# durtest-ripup.net
KiCad netlist of a schematic drawn in EAGLE
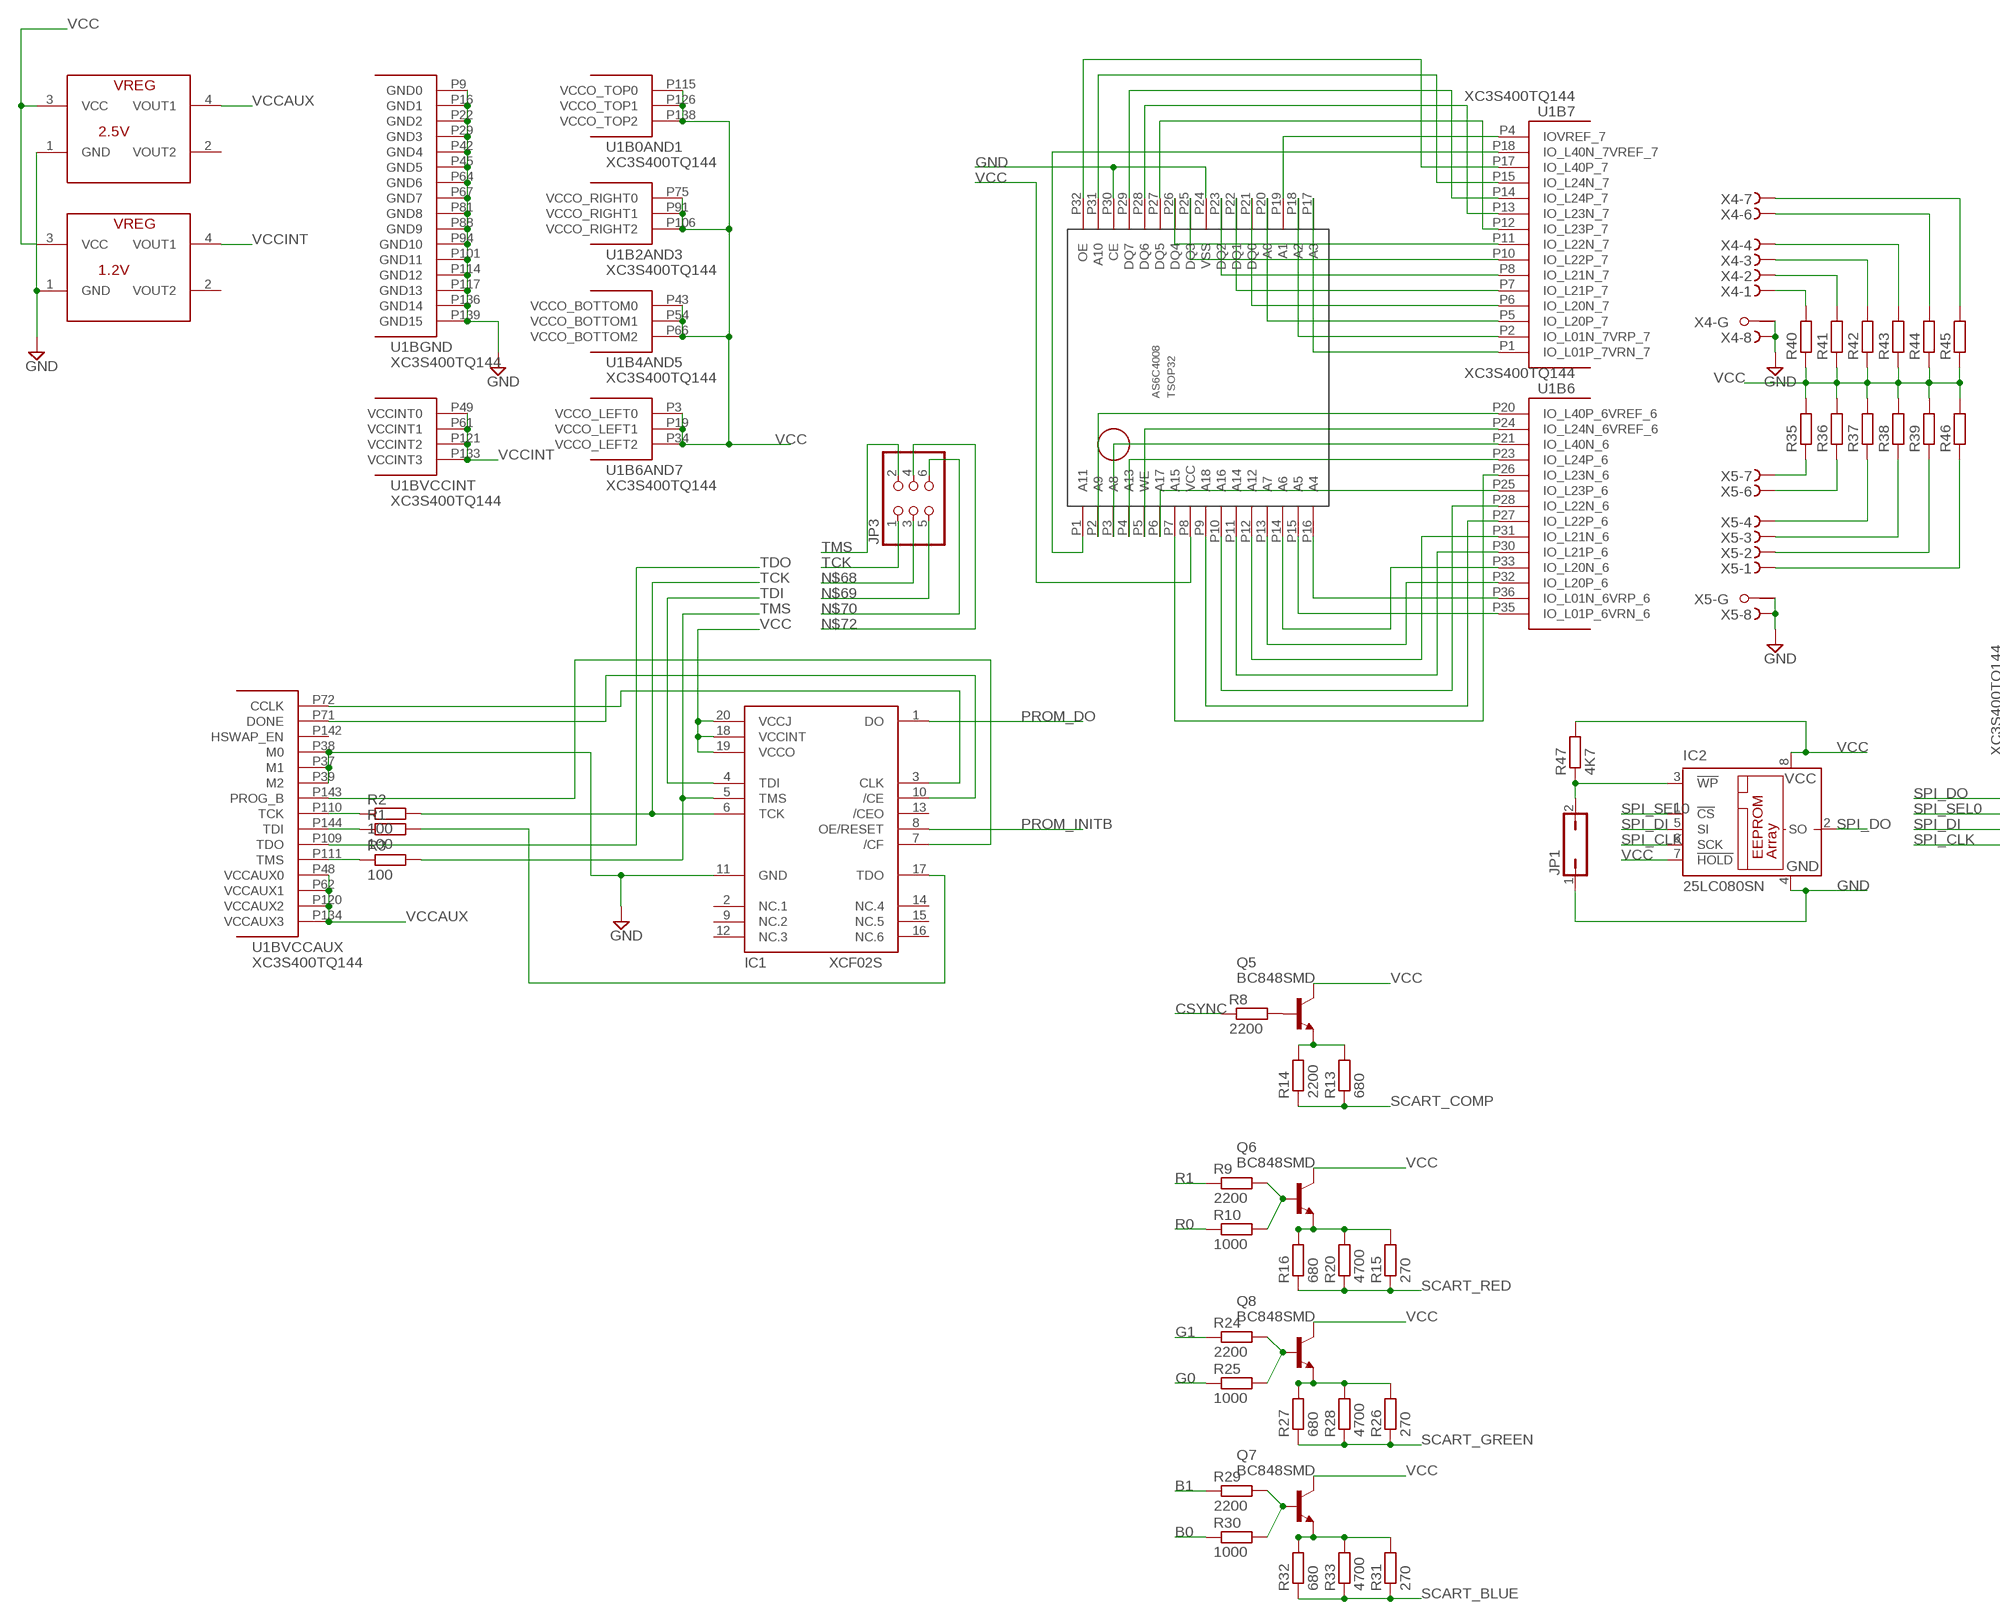
[diagram p0: schematic, sheet 1, part 1 of 2]
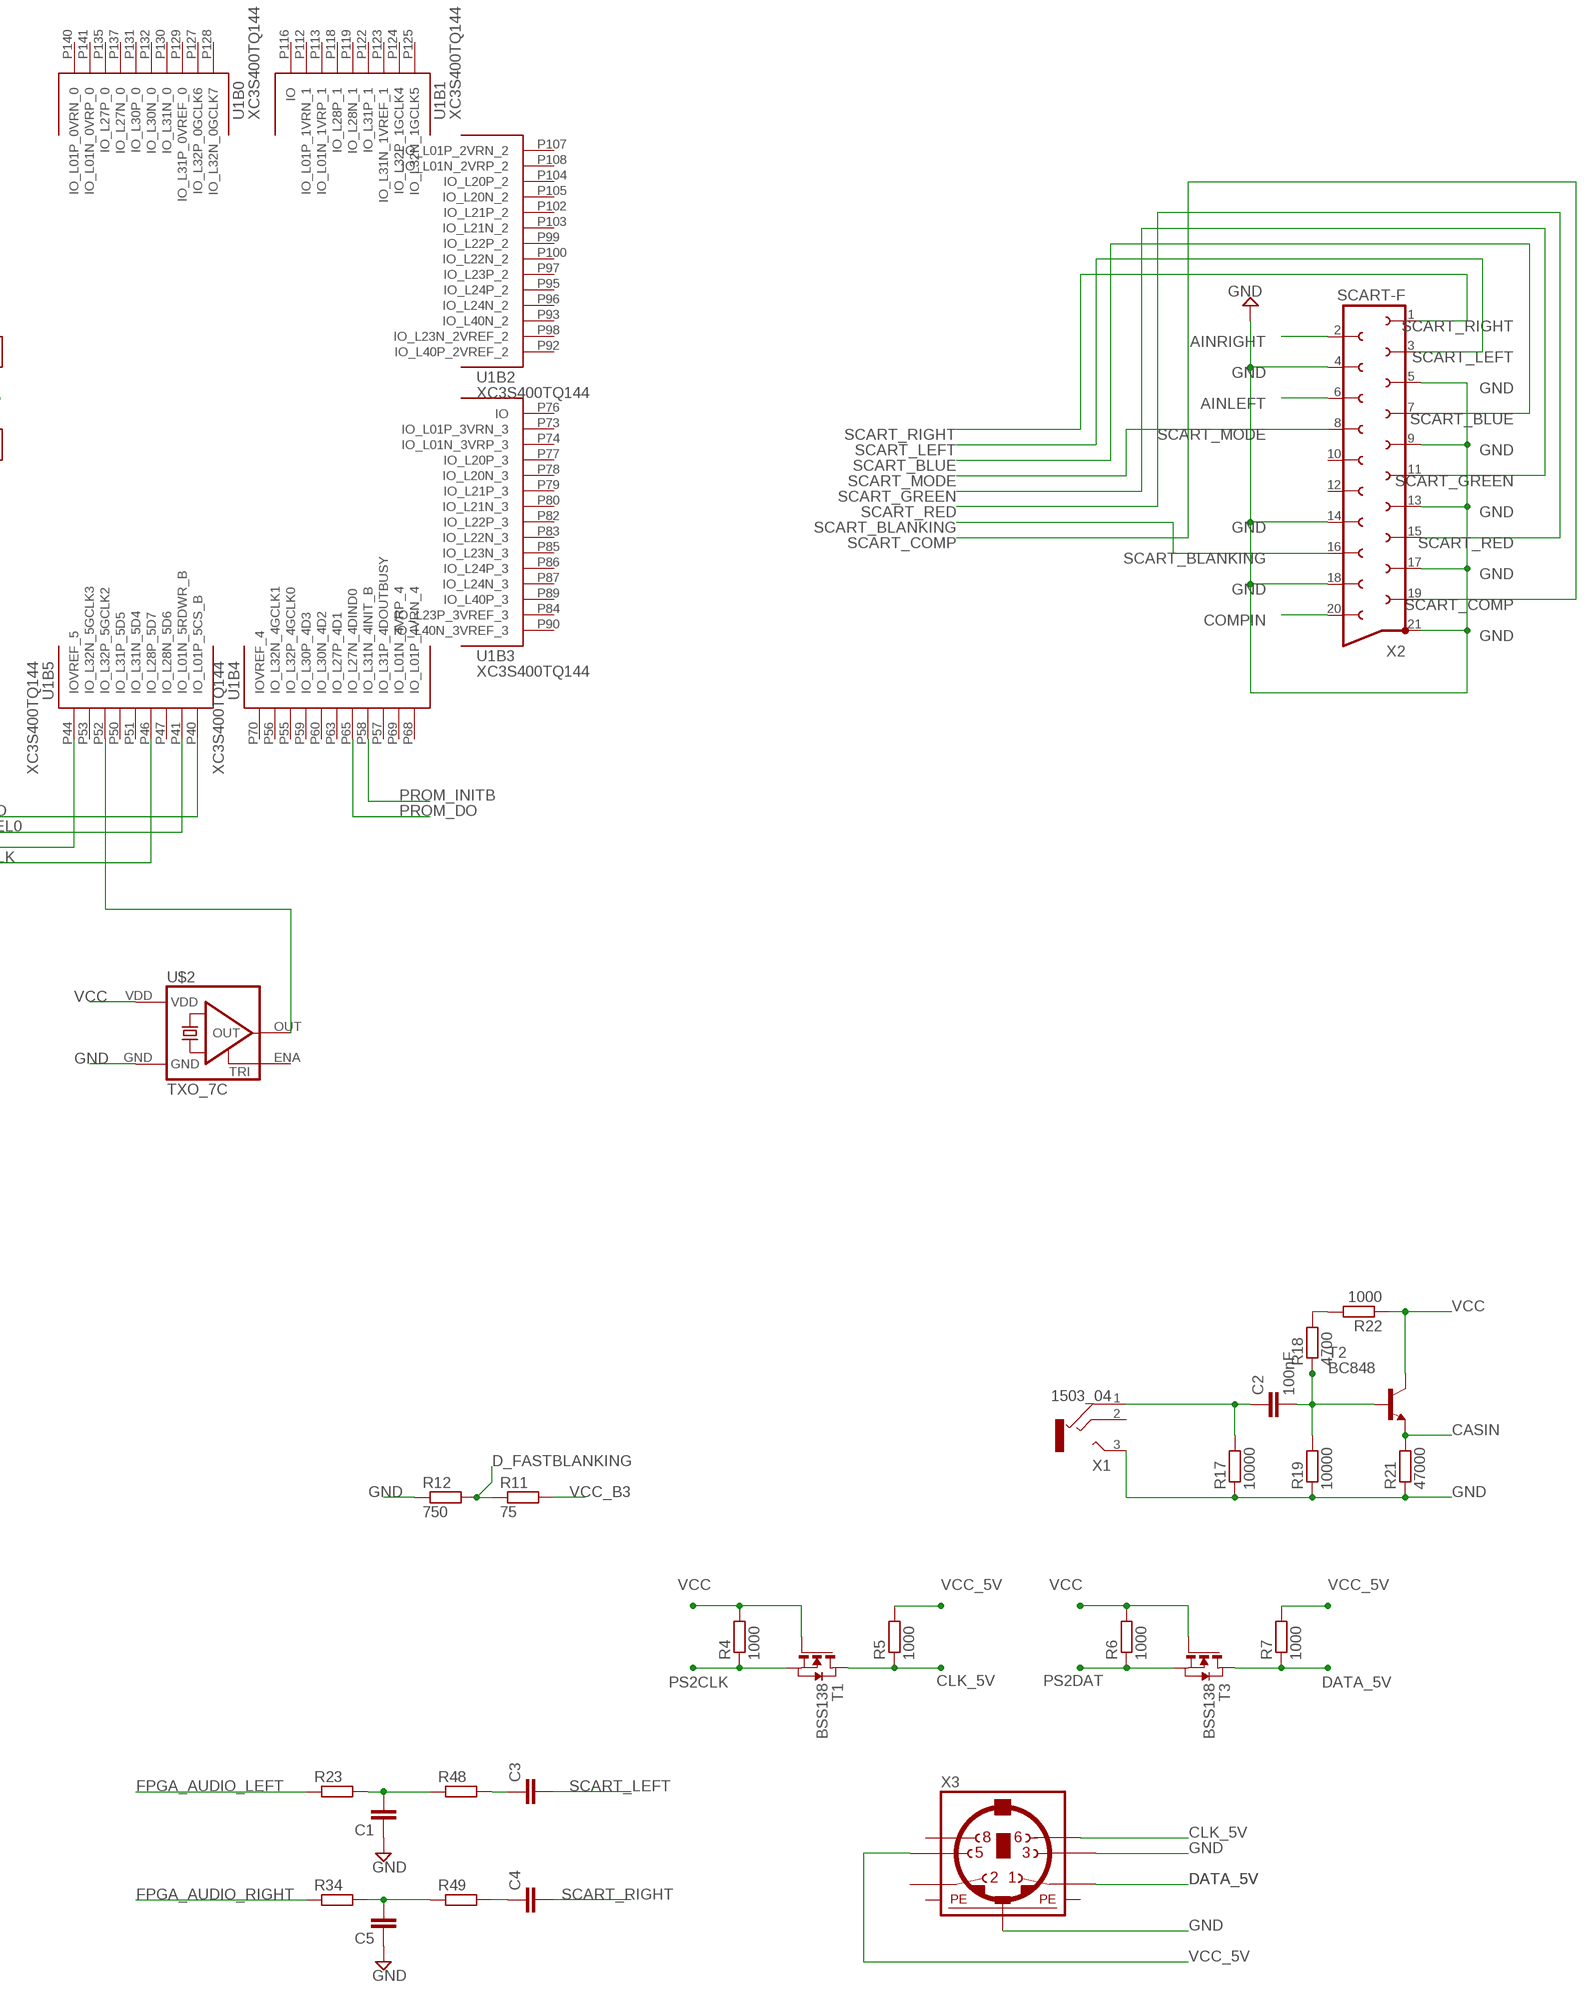
[diagram p1: schematic, sheet 1, part 2 of 2]

(export (version "E")
  (design (tool "Eeschema 10.0.6"))
  (components
    (comp (ref "C1")
      (value "C-EUC0603")
      (footprint "eagle-import:C0603")
      (libsource (lib "eagle-import") (part "C-EUC0603"))
    )
    (comp (ref "C2")
      (value "100nF")
      (footprint "eagle-import:C0603")
      (libsource (lib "eagle-import") (part "C-EUC0603"))
    )
    (comp (ref "C3")
      (value "C-EUC0603")
      (footprint "eagle-import:C0603")
      (libsource (lib "eagle-import") (part "C-EUC0603"))
    )
    (comp (ref "C4")
      (value "C-EUC0603")
      (footprint "eagle-import:C0603")
      (libsource (lib "eagle-import") (part "C-EUC0603"))
    )
    (comp (ref "C5")
      (value "C-EUC0603")
      (footprint "eagle-import:C0603")
      (libsource (lib "eagle-import") (part "C-EUC0603"))
    )
    (comp (ref "IC1")
      (value "XCF02S")
      (footprint "eagle-import:VO20")
      (libsource (lib "eagle-import") (part "XCF02S"))
    )
    (comp (ref "IC2")
      (value "25LC080SN")
      (footprint "eagle-import:SO-08")
      (fields (field (name "MF") "MICROCHIP") (field (name "MPN") "25LC080/SN"))
      (libsource (lib "eagle-import") (part "25SNLC080"))
    )
    (comp (ref "JP1")
      (value "JP1Q")
      (footprint "eagle-import:JP1")
      (libsource (lib "eagle-import") (part "JP1Q"))
    )
    (comp (ref "JP3")
      (value "PINHD-2X3")
      (footprint "eagle-import:2X03")
      (libsource (lib "eagle-import") (part "PINHD-2X3"))
    )
    (comp (ref "Q5")
      (value "BC848SMD")
      (footprint "eagle-import:SOT23")
      (libsource (lib "eagle-import") (part "BC848SMD"))
    )
    (comp (ref "Q6")
      (value "BC848SMD")
      (footprint "eagle-import:SOT23")
      (libsource (lib "eagle-import") (part "BC848SMD"))
    )
    (comp (ref "Q7")
      (value "BC848SMD")
      (footprint "eagle-import:SOT23")
      (libsource (lib "eagle-import") (part "BC848SMD"))
    )
    (comp (ref "Q8")
      (value "BC848SMD")
      (footprint "eagle-import:SOT23")
      (libsource (lib "eagle-import") (part "BC848SMD"))
    )
    (comp (ref "R1")
      (value "100")
      (footprint "eagle-import:R0805")
      (libsource (lib "eagle-import") (part "R-EU_R0805"))
    )
    (comp (ref "R2")
      (value "100")
      (footprint "eagle-import:R0805")
      (libsource (lib "eagle-import") (part "R-EU_R0805"))
    )
    (comp (ref "R3")
      (value "100")
      (footprint "eagle-import:R0805")
      (libsource (lib "eagle-import") (part "R-EU_R0805"))
    )
    (comp (ref "R4")
      (value "1000")
      (footprint "eagle-import:R0805")
      (libsource (lib "eagle-import") (part "R-EU_R0805"))
    )
    (comp (ref "R5")
      (value "1000")
      (footprint "eagle-import:R0805")
      (libsource (lib "eagle-import") (part "R-EU_R0805"))
    )
    (comp (ref "R6")
      (value "1000")
      (footprint "eagle-import:R0805")
      (libsource (lib "eagle-import") (part "R-EU_R0805"))
    )
    (comp (ref "R7")
      (value "1000")
      (footprint "eagle-import:R0805")
      (libsource (lib "eagle-import") (part "R-EU_R0805"))
    )
    (comp (ref "R8")
      (value "2200")
      (footprint "eagle-import:R0805")
      (libsource (lib "eagle-import") (part "R-EU_R0805"))
    )
    (comp (ref "R9")
      (value "2200")
      (footprint "eagle-import:R0805")
      (libsource (lib "eagle-import") (part "R-EU_R0805"))
    )
    (comp (ref "R10")
      (value "1000")
      (footprint "eagle-import:R0805")
      (libsource (lib "eagle-import") (part "R-EU_R0805"))
    )
    (comp (ref "R11")
      (value "75")
      (footprint "eagle-import:R0805")
      (libsource (lib "eagle-import") (part "R-EU_R0805"))
    )
    (comp (ref "R12")
      (value "750")
      (footprint "eagle-import:R0805")
      (libsource (lib "eagle-import") (part "R-EU_R0805"))
    )
    (comp (ref "R13")
      (value "680")
      (footprint "eagle-import:R0805")
      (libsource (lib "eagle-import") (part "R-EU_R0805"))
    )
    (comp (ref "R14")
      (value "2200")
      (footprint "eagle-import:R0805")
      (libsource (lib "eagle-import") (part "R-EU_R0805"))
    )
    (comp (ref "R15")
      (value "270")
      (footprint "eagle-import:R0805")
      (libsource (lib "eagle-import") (part "R-EU_R0805"))
    )
    (comp (ref "R16")
      (value "680")
      (footprint "eagle-import:R0805")
      (libsource (lib "eagle-import") (part "R-EU_R0805"))
    )
    (comp (ref "R17")
      (value "10000")
      (footprint "eagle-import:R0805")
      (libsource (lib "eagle-import") (part "R-EU_R0805"))
    )
    (comp (ref "R18")
      (value "4700")
      (footprint "eagle-import:R0805")
      (libsource (lib "eagle-import") (part "R-EU_R0805"))
    )
    (comp (ref "R19")
      (value "10000")
      (footprint "eagle-import:R0805")
      (libsource (lib "eagle-import") (part "R-EU_R0805"))
    )
    (comp (ref "R20")
      (value "4700")
      (footprint "eagle-import:R0805")
      (libsource (lib "eagle-import") (part "R-EU_R0805"))
    )
    (comp (ref "R21")
      (value "47000")
      (footprint "eagle-import:R0805")
      (libsource (lib "eagle-import") (part "R-EU_R0805"))
    )
    (comp (ref "R22")
      (value "1000")
      (footprint "eagle-import:R0805")
      (libsource (lib "eagle-import") (part "R-EU_R0805"))
    )
    (comp (ref "R23")
      (value "R-EU_M0805")
      (footprint "eagle-import:M0805")
      (libsource (lib "eagle-import") (part "resistor_R-EU_M0805"))
    )
    (comp (ref "R24")
      (value "2200")
      (footprint "eagle-import:R0805")
      (libsource (lib "eagle-import") (part "R-EU_R0805"))
    )
    (comp (ref "R25")
      (value "1000")
      (footprint "eagle-import:R0805")
      (libsource (lib "eagle-import") (part "R-EU_R0805"))
    )
    (comp (ref "R26")
      (value "270")
      (footprint "eagle-import:R0805")
      (libsource (lib "eagle-import") (part "R-EU_R0805"))
    )
    (comp (ref "R27")
      (value "680")
      (footprint "eagle-import:R0805")
      (libsource (lib "eagle-import") (part "R-EU_R0805"))
    )
    (comp (ref "R28")
      (value "4700")
      (footprint "eagle-import:R0805")
      (libsource (lib "eagle-import") (part "R-EU_R0805"))
    )
    (comp (ref "R29")
      (value "2200")
      (footprint "eagle-import:R0805")
      (libsource (lib "eagle-import") (part "R-EU_R0805"))
    )
    (comp (ref "R30")
      (value "1000")
      (footprint "eagle-import:R0805")
      (libsource (lib "eagle-import") (part "R-EU_R0805"))
    )
    (comp (ref "R31")
      (value "270")
      (footprint "eagle-import:R0805")
      (libsource (lib "eagle-import") (part "R-EU_R0805"))
    )
    (comp (ref "R32")
      (value "680")
      (footprint "eagle-import:R0805")
      (libsource (lib "eagle-import") (part "R-EU_R0805"))
    )
    (comp (ref "R33")
      (value "4700")
      (footprint "eagle-import:R0805")
      (libsource (lib "eagle-import") (part "R-EU_R0805"))
    )
    (comp (ref "R34")
      (value "R-EU_M0805")
      (footprint "eagle-import:M0805")
      (libsource (lib "eagle-import") (part "resistor_R-EU_M0805"))
    )
    (comp (ref "R35")
      (value "R-EU_M0805")
      (footprint "eagle-import:M0805")
      (libsource (lib "eagle-import") (part "resistor_R-EU_M0805"))
    )
    (comp (ref "R36")
      (value "R-EU_M0805")
      (footprint "eagle-import:M0805")
      (libsource (lib "eagle-import") (part "resistor_R-EU_M0805"))
    )
    (comp (ref "R37")
      (value "R-EU_M0805")
      (footprint "eagle-import:M0805")
      (libsource (lib "eagle-import") (part "resistor_R-EU_M0805"))
    )
    (comp (ref "R38")
      (value "R-EU_M0805")
      (footprint "eagle-import:M0805")
      (libsource (lib "eagle-import") (part "resistor_R-EU_M0805"))
    )
    (comp (ref "R39")
      (value "R-EU_M0805")
      (footprint "eagle-import:M0805")
      (libsource (lib "eagle-import") (part "resistor_R-EU_M0805"))
    )
    (comp (ref "R40")
      (value "R-EU_M0805")
      (footprint "eagle-import:M0805")
      (libsource (lib "eagle-import") (part "resistor_R-EU_M0805"))
    )
    (comp (ref "R41")
      (value "R-EU_M0805")
      (footprint "eagle-import:M0805")
      (libsource (lib "eagle-import") (part "resistor_R-EU_M0805"))
    )
    (comp (ref "R42")
      (value "R-EU_M0805")
      (footprint "eagle-import:M0805")
      (libsource (lib "eagle-import") (part "resistor_R-EU_M0805"))
    )
    (comp (ref "R43")
      (value "R-EU_M0805")
      (footprint "eagle-import:M0805")
      (libsource (lib "eagle-import") (part "resistor_R-EU_M0805"))
    )
    (comp (ref "R44")
      (value "R-EU_M0805")
      (footprint "eagle-import:M0805")
      (libsource (lib "eagle-import") (part "resistor_R-EU_M0805"))
    )
    (comp (ref "R45")
      (value "R-EU_M0805")
      (footprint "eagle-import:M0805")
      (libsource (lib "eagle-import") (part "resistor_R-EU_M0805"))
    )
    (comp (ref "R46")
      (value "R-EU_M0805")
      (footprint "eagle-import:M0805")
      (libsource (lib "eagle-import") (part "resistor_R-EU_M0805"))
    )
    (comp (ref "R47")
      (value "4K7")
      (footprint "eagle-import:R0805")
      (libsource (lib "eagle-import") (part "R-EU_R0805"))
    )
    (comp (ref "R48")
      (value "R-EU_M0805")
      (footprint "eagle-import:M0805")
      (libsource (lib "eagle-import") (part "resistor_R-EU_M0805"))
    )
    (comp (ref "R49")
      (value "R-EU_M0805")
      (footprint "eagle-import:M0805")
      (libsource (lib "eagle-import") (part "resistor_R-EU_M0805"))
    )
    (comp (ref "REG1.2")
      (value "1.2V")
      (footprint "eagle-import:SOT223")
      (libsource (lib "eagle-import") (part "NX1117"))
    )
    (comp (ref "REG2.5")
      (value "2.5V")
      (footprint "eagle-import:SOT223")
      (libsource (lib "eagle-import") (part "NX1117"))
    )
    (comp (ref "T1")
      (value "BSS138")
      (footprint "eagle-import:SOT-23")
      (libsource (lib "eagle-import") (part "NMOSSOT23"))
    )
    (comp (ref "T2")
      (value "BC848")
      (footprint "eagle-import:SOT23")
      (libsource (lib "eagle-import") (part "BC848"))
    )
    (comp (ref "T3")
      (value "BSS138")
      (footprint "eagle-import:SOT-23")
      (libsource (lib "eagle-import") (part "NMOSSOT23"))
    )
    (comp (ref "U$1")
      (value "AS6C4008")
      (footprint "eagle-import:TSOP32")
      (libsource (lib "eagle-import") (part "AS6C4008"))
    )
    (comp (ref "U$2")
      (value "TXO_7C")
      (footprint "eagle-import:OSC_7C")
      (libsource (lib "eagle-import") (part "TXO_7C"))
    )
    (comp (ref "U1")
      (value "XC3S400TQ144")
      (footprint "eagle-import:TQ144")
      (libsource (lib "eagle-import") (part "XC3S400TQ144"))
    )
    (comp (ref "X1")
      (value "1503_04")
      (footprint "eagle-import:1503_04")
      (libsource (lib "eagle-import") (part "1503_04"))
    )
    (comp (ref "X2")
      (value "SCART-F")
      (footprint "eagle-import:SCART-F")
      (libsource (lib "eagle-import") (part "SCART-F"))
    )
    (comp (ref "X3")
      (value "MINI_DIN_6")
      (footprint "eagle-import:M_DIN6")
      (libsource (lib "eagle-import") (part "MINI_DIN_6"))
    )
    (comp (ref "X4")
      (value "F09HPS")
      (footprint "eagle-import:F09HP")
      (libsource (lib "eagle-import") (part "F09HPS"))
    )
    (comp (ref "X5")
      (value "F09HPS")
      (footprint "eagle-import:F09HP")
      (libsource (lib "eagle-import") (part "F09HPS"))
    )
  )
  (nets
    (net (code "1") (name "/AINLEFT") (class "Default")
      (node (ref "X2") (pin "6") (pinfunction "6_6") (pintype "passive"))
    )
    (net (code "2") (name "/AINRIGHT") (class "Default")
      (node (ref "X2") (pin "2") (pinfunction "2_2") (pintype "passive"))
    )
    (net (code "3") (name "/B0") (class "Default")
      (node (ref "R30") (pin "1") (pinfunction "1_1") (pintype "passive"))
    )
    (net (code "4") (name "/B1") (class "Default")
      (node (ref "R29") (pin "1") (pinfunction "1_1") (pintype "passive"))
    )
    (net (code "5") (name "/CASIN") (class "Default")
      (node (ref "R21") (pin "2") (pinfunction "2_2") (pintype "passive"))
      (node (ref "T2") (pin "2") (pinfunction "E_2") (pintype "passive"))
    )
    (net (code "6") (name "/CLK_5V") (class "Default")
      (node (ref "R5") (pin "1") (pinfunction "1_1") (pintype "passive"))
      (node (ref "T1") (pin "1") (pinfunction "D_1") (pintype "passive"))
      (node (ref "X3") (pin "6") (pinfunction "6_6") (pintype "passive"))
    )
    (net (code "7") (name "/COMPIN") (class "Default")
      (node (ref "X2") (pin "20") (pinfunction "20_20") (pintype "passive"))
    )
    (net (code "8") (name "/CSYNC") (class "Default")
      (node (ref "R8") (pin "1") (pinfunction "1_1") (pintype "passive"))
    )
    (net (code "9") (name "/DATA_5V") (class "Default")
      (node (ref "R7") (pin "1") (pinfunction "1_1") (pintype "passive"))
      (node (ref "T3") (pin "1") (pinfunction "D_1") (pintype "passive"))
      (node (ref "X3") (pin "1") (pinfunction "1_1") (pintype "passive"))
    )
    (net (code "10") (name "/D_FASTBLANKING") (class "Default")
      (node (ref "R11") (pin "1") (pinfunction "1_1") (pintype "passive"))
      (node (ref "R12") (pin "2") (pinfunction "2_2") (pintype "passive"))
    )
    (net (code "11") (name "/FPGA_AUDIO_LEFT") (class "Default")
      (node (ref "R23") (pin "1") (pinfunction "1_1") (pintype "passive"))
    )
    (net (code "12") (name "/FPGA_AUDIO_RIGHT") (class "Default")
      (node (ref "R34") (pin "1") (pinfunction "1_1") (pintype "passive"))
    )
    (net (code "13") (name "/G0") (class "Default")
      (node (ref "R25") (pin "1") (pinfunction "1_1") (pintype "passive"))
    )
    (net (code "14") (name "/G1") (class "Default")
      (node (ref "R24") (pin "1") (pinfunction "1_1") (pintype "passive"))
    )
    (net (code "15") (name "/N$68") (class "Default")
      (node (ref "JP3") (pin "3") (pinfunction "3_3") (pintype "passive"))
    )
    (net (code "16") (name "/N$69") (class "Default")
      (node (ref "JP3") (pin "5") (pinfunction "5_5") (pintype "passive"))
    )
    (net (code "17") (name "/N$70") (class "Default")
      (node (ref "JP3") (pin "6") (pinfunction "6_6") (pintype "passive"))
    )
    (net (code "18") (name "/N$72") (class "Default")
      (node (ref "JP3") (pin "4") (pinfunction "4_4") (pintype "passive"))
    )
    (net (code "19") (name "/PE1") (class "Default")
      (node (ref "X3") (pin "SH1") (pinfunction "PE1_SH1") (pintype "power_in"))
    )
    (net (code "20") (name "/PE3") (class "Default")
      (node (ref "X3") (pin "SH3") (pinfunction "PE3_SH3") (pintype "power_in"))
    )
    (net (code "21") (name "/PROM_DO") (class "Default")
      (node (ref "IC1") (pin "1") (pinfunction "DO_1") (pintype "bidirectional"))
      (node (ref "U1") (pin "P65") (pinfunction "IO_L27N_4DIND0_P65") (pintype "bidirectional"))
    )
    (net (code "22") (name "/PROM_INITB") (class "Default")
      (node (ref "IC1") (pin "8") (pinfunction "OE/RESET_8") (pintype "bidirectional"))
      (node (ref "U1") (pin "P58") (pinfunction "IO_L31N_4INIT_B_P58") (pintype "bidirectional"))
    )
    (net (code "23") (name "/PS2CLK") (class "Default")
      (node (ref "R4") (pin "1") (pinfunction "1_1") (pintype "passive"))
      (node (ref "T1") (pin "2") (pinfunction "S_2") (pintype "passive"))
    )
    (net (code "24") (name "/PS2DAT") (class "Default")
      (node (ref "R6") (pin "1") (pinfunction "1_1") (pintype "passive"))
      (node (ref "T3") (pin "2") (pinfunction "S_2") (pintype "passive"))
    )
    (net (code "25") (name "/R0") (class "Default")
      (node (ref "R10") (pin "1") (pinfunction "1_1") (pintype "passive"))
    )
    (net (code "26") (name "/R1") (class "Default")
      (node (ref "R9") (pin "1") (pinfunction "1_1") (pintype "passive"))
    )
    (net (code "27") (name "/SCART_BLANKING") (class "Default")
      (node (ref "X2") (pin "16") (pinfunction "16_16") (pintype "passive"))
    )
    (net (code "28") (name "/SCART_BLUE") (class "Default")
      (node (ref "R31") (pin "1") (pinfunction "1_1") (pintype "passive"))
      (node (ref "R32") (pin "1") (pinfunction "1_1") (pintype "passive"))
      (node (ref "R33") (pin "1") (pinfunction "1_1") (pintype "passive"))
      (node (ref "X2") (pin "7") (pinfunction "7_7") (pintype "passive"))
    )
    (net (code "29") (name "/SCART_COMP") (class "Default")
      (node (ref "R13") (pin "1") (pinfunction "1_1") (pintype "passive"))
      (node (ref "R14") (pin "1") (pinfunction "1_1") (pintype "passive"))
      (node (ref "X2") (pin "19") (pinfunction "19_19") (pintype "passive"))
    )
    (net (code "30") (name "/SCART_GREEN") (class "Default")
      (node (ref "R26") (pin "1") (pinfunction "1_1") (pintype "passive"))
      (node (ref "R27") (pin "1") (pinfunction "1_1") (pintype "passive"))
      (node (ref "R28") (pin "1") (pinfunction "1_1") (pintype "passive"))
      (node (ref "X2") (pin "11") (pinfunction "11_11") (pintype "passive"))
    )
    (net (code "31") (name "/SCART_LEFT") (class "Default")
      (node (ref "C3") (pin "2") (pinfunction "2_2") (pintype "passive"))
      (node (ref "X2") (pin "3") (pinfunction "3_3") (pintype "passive"))
    )
    (net (code "32") (name "/SCART_MODE") (class "Default")
      (node (ref "X2") (pin "8") (pinfunction "8_8") (pintype "passive"))
    )
    (net (code "33") (name "/SCART_RED") (class "Default")
      (node (ref "R15") (pin "1") (pinfunction "1_1") (pintype "passive"))
      (node (ref "R16") (pin "1") (pinfunction "1_1") (pintype "passive"))
      (node (ref "R20") (pin "1") (pinfunction "1_1") (pintype "passive"))
      (node (ref "X2") (pin "15") (pinfunction "15_15") (pintype "passive"))
    )
    (net (code "34") (name "/SCART_RIGHT") (class "Default")
      (node (ref "C4") (pin "2") (pinfunction "2_2") (pintype "passive"))
      (node (ref "X2") (pin "1") (pinfunction "1_1") (pintype "passive"))
    )
    (net (code "35") (name "/SPI_CLK") (class "Default")
      (node (ref "IC2") (pin "6") (pinfunction "SCK_6") (pintype "input"))
      (node (ref "U1") (pin "P46") (pinfunction "IO_L28P_5D7_P46") (pintype "bidirectional"))
    )
    (net (code "36") (name "/SPI_DI") (class "Default")
      (node (ref "IC2") (pin "5") (pinfunction "SI_5") (pintype "input"))
      (node (ref "U1") (pin "P44") (pinfunction "IOVREF_5_P44") (pintype "bidirectional"))
    )
    (net (code "37") (name "/SPI_DO") (class "Default")
      (node (ref "IC2") (pin "2") (pinfunction "SO_2") (pintype "bidirectional"))
      (node (ref "U1") (pin "P40") (pinfunction "IO_L01P_5CS_B_P40") (pintype "bidirectional"))
    )
    (net (code "38") (name "/SPI_SEL0") (class "Default")
      (node (ref "IC2") (pin "1") (pinfunction "~{CS}_1") (pintype "input"))
      (node (ref "U1") (pin "P41") (pinfunction "IO_L01N_5RDWR_B_P41") (pintype "bidirectional"))
    )
    (net (code "39") (name "/TCK") (class "Default")
      (node (ref "IC1") (pin "6") (pinfunction "TCK_6") (pintype "bidirectional"))
      (node (ref "JP3") (pin "1") (pinfunction "1_1") (pintype "passive"))
      (node (ref "R2") (pin "2") (pinfunction "2_2") (pintype "passive"))
    )
    (net (code "40") (name "/TDI") (class "Default")
      (node (ref "IC1") (pin "4") (pinfunction "TDI_4") (pintype "bidirectional"))
    )
    (net (code "41") (name "/TDO") (class "Default")
      (node (ref "U1") (pin "P109") (pinfunction "TDO_P109") (pintype "bidirectional"))
    )
    (net (code "42") (name "/TMS") (class "Default")
      (node (ref "IC1") (pin "5") (pinfunction "TMS_5") (pintype "bidirectional"))
      (node (ref "JP3") (pin "2") (pinfunction "2_2") (pintype "passive"))
      (node (ref "R3") (pin "2") (pinfunction "2_2") (pintype "passive"))
    )
    (net (code "43") (name "/VCC") (class "Default")
      (node (ref "IC1") (pin "18") (pinfunction "VCCINT_18") (pintype "bidirectional"))
      (node (ref "IC1") (pin "19") (pinfunction "VCCO_19") (pintype "bidirectional"))
      (node (ref "IC1") (pin "20") (pinfunction "VCCJ_20") (pintype "bidirectional"))
      (node (ref "IC2") (pin "7") (pinfunction "~{HOLD}_7") (pintype "input"))
      (node (ref "IC2") (pin "8") (pinfunction "VCC_8") (pintype "power_in"))
      (node (ref "Q5") (pin "3") (pinfunction "C_3") (pintype "passive"))
      (node (ref "Q6") (pin "3") (pinfunction "C_3") (pintype "passive"))
      (node (ref "Q7") (pin "3") (pinfunction "C_3") (pintype "passive"))
      (node (ref "Q8") (pin "3") (pinfunction "C_3") (pintype "passive"))
      (node (ref "R22") (pin "1") (pinfunction "1_1") (pintype "passive"))
      (node (ref "R35") (pin "2") (pinfunction "2_2") (pintype "passive"))
      (node (ref "R36") (pin "2") (pinfunction "2_2") (pintype "passive"))
      (node (ref "R37") (pin "2") (pinfunction "2_2") (pintype "passive"))
      (node (ref "R38") (pin "2") (pinfunction "2_2") (pintype "passive"))
      (node (ref "R39") (pin "2") (pinfunction "2_2") (pintype "passive"))
      (node (ref "R4") (pin "2") (pinfunction "2_2") (pintype "passive"))
      (node (ref "R40") (pin "1") (pinfunction "1_1") (pintype "passive"))
      (node (ref "R41") (pin "1") (pinfunction "1_1") (pintype "passive"))
      (node (ref "R42") (pin "1") (pinfunction "1_1") (pintype "passive"))
      (node (ref "R43") (pin "1") (pinfunction "1_1") (pintype "passive"))
      (node (ref "R44") (pin "1") (pinfunction "1_1") (pintype "passive"))
      (node (ref "R45") (pin "1") (pinfunction "1_1") (pintype "passive"))
      (node (ref "R46") (pin "2") (pinfunction "2_2") (pintype "passive"))
      (node (ref "R47") (pin "2") (pinfunction "2_2") (pintype "passive"))
      (node (ref "R6") (pin "2") (pinfunction "2_2") (pintype "passive"))
      (node (ref "REG1.2") (pin "3") (pinfunction "VCC_3") (pintype "bidirectional"))
      (node (ref "REG2.5") (pin "3") (pinfunction "VCC_3") (pintype "bidirectional"))
      (node (ref "T1") (pin "3") (pinfunction "G_3") (pintype "passive"))
      (node (ref "T2") (pin "3") (pinfunction "C_3") (pintype "passive"))
      (node (ref "T3") (pin "3") (pinfunction "G_3") (pintype "passive"))
      (node (ref "U$1") (pin "P8") (pinfunction "VCC_P8") (pintype "bidirectional"))
      (node (ref "U$2") (pin "VDD") (pinfunction "VDD_VDD") (pintype "power_in"))
      (node (ref "U1") (pin "P106") (pinfunction "VCCO_RIGHT2_P106") (pintype "passive"))
      (node (ref "U1") (pin "P115") (pinfunction "VCCO_TOP0_P115") (pintype "passive"))
      (node (ref "U1") (pin "P126") (pinfunction "VCCO_TOP1_P126") (pintype "passive"))
      (node (ref "U1") (pin "P138") (pinfunction "VCCO_TOP2_P138") (pintype "passive"))
      (node (ref "U1") (pin "P19") (pinfunction "VCCO_LEFT1_P19") (pintype "passive"))
      (node (ref "U1") (pin "P3") (pinfunction "VCCO_LEFT0_P3") (pintype "passive"))
      (node (ref "U1") (pin "P34") (pinfunction "VCCO_LEFT2_P34") (pintype "passive"))
      (node (ref "U1") (pin "P43") (pinfunction "VCCO_BOTTOM0_P43") (pintype "passive"))
      (node (ref "U1") (pin "P54") (pinfunction "VCCO_BOTTOM1_P54") (pintype "passive"))
      (node (ref "U1") (pin "P66") (pinfunction "VCCO_BOTTOM2_P66") (pintype "passive"))
      (node (ref "U1") (pin "P75") (pinfunction "VCCO_RIGHT0_P75") (pintype "passive"))
      (node (ref "U1") (pin "P91") (pinfunction "VCCO_RIGHT1_P91") (pintype "passive"))
    )
    (net (code "44") (name "/VCCAUX") (class "Default")
      (node (ref "REG2.5") (pin "4") (pinfunction "VOUT1_4") (pintype "bidirectional"))
      (node (ref "U1") (pin "P120") (pinfunction "VCCAUX2_P120") (pintype "passive"))
      (node (ref "U1") (pin "P134") (pinfunction "VCCAUX3_P134") (pintype "passive"))
      (node (ref "U1") (pin "P48") (pinfunction "VCCAUX0_P48") (pintype "passive"))
      (node (ref "U1") (pin "P62") (pinfunction "VCCAUX1_P62") (pintype "passive"))
    )
    (net (code "45") (name "/VCCINT") (class "Default")
      (node (ref "REG1.2") (pin "4") (pinfunction "VOUT1_4") (pintype "bidirectional"))
      (node (ref "U1") (pin "P121") (pinfunction "VCCINT2_P121") (pintype "passive"))
      (node (ref "U1") (pin "P133") (pinfunction "VCCINT3_P133") (pintype "passive"))
      (node (ref "U1") (pin "P49") (pinfunction "VCCINT0_P49") (pintype "passive"))
      (node (ref "U1") (pin "P61") (pinfunction "VCCINT1_P61") (pintype "passive"))
    )
    (net (code "46") (name "/VCC_5V") (class "Default")
      (node (ref "R5") (pin "2") (pinfunction "2_2") (pintype "passive"))
      (node (ref "R7") (pin "2") (pinfunction "2_2") (pintype "passive"))
      (node (ref "X3") (pin "5") (pinfunction "5_5") (pintype "passive"))
    )
    (net (code "47") (name "/VCC_B3") (class "Default")
      (node (ref "R11") (pin "2") (pinfunction "2_2") (pintype "passive"))
    )
    (net (code "48") (name "GND") (class "Default")
      (node (ref "C1") (pin "1") (pinfunction "1_1") (pintype "passive"))
      (node (ref "C5") (pin "1") (pinfunction "1_1") (pintype "passive"))
      (node (ref "IC1") (pin "11") (pinfunction "GND_11") (pintype "bidirectional"))
      (node (ref "IC2") (pin "4") (pinfunction "GND_4") (pintype "power_in"))
      (node (ref "JP1") (pin "1") (pinfunction "1_1") (pintype "passive"))
      (node (ref "R12") (pin "1") (pinfunction "1_1") (pintype "passive"))
      (node (ref "R17") (pin "1") (pinfunction "1_1") (pintype "passive"))
      (node (ref "R19") (pin "1") (pinfunction "1_1") (pintype "passive"))
      (node (ref "R21") (pin "1") (pinfunction "1_1") (pintype "passive"))
      (node (ref "REG1.2") (pin "1") (pinfunction "GND_1") (pintype "bidirectional"))
      (node (ref "REG2.5") (pin "1") (pinfunction "GND_1") (pintype "bidirectional"))
      (node (ref "U$1") (pin "P24") (pinfunction "VSS_P24") (pintype "bidirectional"))
      (node (ref "U$1") (pin "P30") (pinfunction "CE_P30") (pintype "bidirectional"))
      (node (ref "U$2") (pin "GND") (pinfunction "GND_GND") (pintype "power_in"))
      (node (ref "U1") (pin "P101") (pinfunction "GND11_P101") (pintype "passive"))
      (node (ref "U1") (pin "P114") (pinfunction "GND12_P114") (pintype "passive"))
      (node (ref "U1") (pin "P117") (pinfunction "GND13_P117") (pintype "passive"))
      (node (ref "U1") (pin "P136") (pinfunction "GND14_P136") (pintype "passive"))
      (node (ref "U1") (pin "P139") (pinfunction "GND15_P139") (pintype "passive"))
      (node (ref "U1") (pin "P16") (pinfunction "GND1_P16") (pintype "passive"))
      (node (ref "U1") (pin "P22") (pinfunction "GND2_P22") (pintype "passive"))
      (node (ref "U1") (pin "P29") (pinfunction "GND3_P29") (pintype "passive"))
      (node (ref "U1") (pin "P37") (pinfunction "M1_P37") (pintype "bidirectional"))
      (node (ref "U1") (pin "P38") (pinfunction "M0_P38") (pintype "bidirectional"))
      (node (ref "U1") (pin "P39") (pinfunction "M2_P39") (pintype "bidirectional"))
      (node (ref "U1") (pin "P42") (pinfunction "GND4_P42") (pintype "passive"))
      (node (ref "U1") (pin "P45") (pinfunction "GND5_P45") (pintype "passive"))
      (node (ref "U1") (pin "P64") (pinfunction "GND6_P64") (pintype "passive"))
      (node (ref "U1") (pin "P67") (pinfunction "GND7_P67") (pintype "passive"))
      (node (ref "U1") (pin "P81") (pinfunction "GND8_P81") (pintype "passive"))
      (node (ref "U1") (pin "P88") (pinfunction "GND9_P88") (pintype "passive"))
      (node (ref "U1") (pin "P9") (pinfunction "GND0_P9") (pintype "passive"))
      (node (ref "U1") (pin "P94") (pinfunction "GND10_P94") (pintype "passive"))
      (node (ref "X1") (pin "3") (pinfunction "2_3") (pintype "passive"))
      (node (ref "X2") (pin "13") (pinfunction "13_13") (pintype "passive"))
      (node (ref "X2") (pin "14") (pinfunction "14_14") (pintype "passive"))
      (node (ref "X2") (pin "17") (pinfunction "17_17") (pintype "passive"))
      (node (ref "X2") (pin "18") (pinfunction "18_18") (pintype "passive"))
      (node (ref "X2") (pin "21") (pinfunction "21_21") (pintype "passive"))
      (node (ref "X2") (pin "4") (pinfunction "4_4") (pintype "passive"))
      (node (ref "X2") (pin "5") (pinfunction "5_5") (pintype "passive"))
      (node (ref "X2") (pin "9") (pinfunction "9_9") (pintype "passive"))
      (node (ref "X3") (pin "3") (pinfunction "3_3") (pintype "passive"))
      (node (ref "X3") (pin "SH2") (pinfunction "PE2_SH2") (pintype "power_in"))
      (node (ref "X4") (pin "8") (pinfunction "F_8") (pintype "passive"))
      (node (ref "X4") (pin "G1") (pinfunction "G1_G1") (pintype "passive"))
      (node (ref "X5") (pin "8") (pinfunction "F_8") (pintype "passive"))
      (node (ref "X5") (pin "G1") (pinfunction "G1_G1") (pintype "passive"))
    )
    (net (code "49") (name "Net-(C1-Pad2)") (class "Default")
      (node (ref "C1") (pin "2") (pinfunction "2_2") (pintype "passive"))
      (node (ref "R23") (pin "2") (pinfunction "2_2") (pintype "passive"))
      (node (ref "R48") (pin "1") (pinfunction "1_1") (pintype "passive"))
    )
    (net (code "50") (name "Net-(C2-Pad1)") (class "Default")
      (node (ref "C2") (pin "1") (pinfunction "1_1") (pintype "passive"))
      (node (ref "R17") (pin "2") (pinfunction "2_2") (pintype "passive"))
      (node (ref "X1") (pin "1") (pinfunction "1_1") (pintype "passive"))
    )
    (net (code "51") (name "Net-(C3-Pad1)") (class "Default")
      (node (ref "C3") (pin "1") (pinfunction "1_1") (pintype "passive"))
      (node (ref "R48") (pin "2") (pinfunction "2_2") (pintype "passive"))
    )
    (net (code "52") (name "Net-(C4-Pad1)") (class "Default")
      (node (ref "C4") (pin "1") (pinfunction "1_1") (pintype "passive"))
      (node (ref "R49") (pin "2") (pinfunction "2_2") (pintype "passive"))
    )
    (net (code "53") (name "Net-(C5-Pad2)") (class "Default")
      (node (ref "C5") (pin "2") (pinfunction "2_2") (pintype "passive"))
      (node (ref "R34") (pin "2") (pinfunction "2_2") (pintype "passive"))
      (node (ref "R49") (pin "1") (pinfunction "1_1") (pintype "passive"))
    )
    (net (code "54") (name "Net-(IC1-CLK)") (class "Default")
      (node (ref "IC1") (pin "3") (pinfunction "CLK_3") (pintype "bidirectional"))
      (node (ref "U1") (pin "P72") (pinfunction "CCLK_P72") (pintype "bidirectional"))
    )
    (net (code "55") (name "Net-(IC1-TDO)") (class "Default")
      (node (ref "IC1") (pin "17") (pinfunction "TDO_17") (pintype "bidirectional"))
      (node (ref "R1") (pin "2") (pinfunction "2_2") (pintype "passive"))
    )
    (net (code "56") (name "Net-(IC1-{slash}CE)") (class "Default")
      (node (ref "IC1") (pin "10") (pinfunction "/CE_10") (pintype "bidirectional"))
      (node (ref "U1") (pin "P71") (pinfunction "DONE_P71") (pintype "bidirectional"))
    )
    (net (code "57") (name "Net-(IC1-{slash}CF)") (class "Default")
      (node (ref "IC1") (pin "7") (pinfunction "/CF_7") (pintype "bidirectional"))
      (node (ref "U1") (pin "P143") (pinfunction "PROG_B_P143") (pintype "bidirectional"))
    )
    (net (code "58") (name "Net-(IC2-~{WP})") (class "Default")
      (node (ref "IC2") (pin "3") (pinfunction "~{WP}_3") (pintype "input"))
      (node (ref "JP1") (pin "2") (pinfunction "2_2") (pintype "passive"))
      (node (ref "R47") (pin "1") (pinfunction "1_1") (pintype "passive"))
    )
    (net (code "59") (name "Net-(Q5-B)") (class "Default")
      (node (ref "Q5") (pin "1") (pinfunction "B_1") (pintype "passive"))
      (node (ref "R8") (pin "2") (pinfunction "2_2") (pintype "passive"))
    )
    (net (code "60") (name "Net-(Q5-E)") (class "Default")
      (node (ref "Q5") (pin "2") (pinfunction "E_2") (pintype "passive"))
      (node (ref "R13") (pin "2") (pinfunction "2_2") (pintype "passive"))
      (node (ref "R14") (pin "2") (pinfunction "2_2") (pintype "passive"))
    )
    (net (code "61") (name "Net-(Q6-B)") (class "Default")
      (node (ref "Q6") (pin "1") (pinfunction "B_1") (pintype "passive"))
      (node (ref "R10") (pin "2") (pinfunction "2_2") (pintype "passive"))
      (node (ref "R9") (pin "2") (pinfunction "2_2") (pintype "passive"))
    )
    (net (code "62") (name "Net-(Q6-E)") (class "Default")
      (node (ref "Q6") (pin "2") (pinfunction "E_2") (pintype "passive"))
      (node (ref "R15") (pin "2") (pinfunction "2_2") (pintype "passive"))
      (node (ref "R16") (pin "2") (pinfunction "2_2") (pintype "passive"))
      (node (ref "R20") (pin "2") (pinfunction "2_2") (pintype "passive"))
    )
    (net (code "63") (name "Net-(Q7-B)") (class "Default")
      (node (ref "Q7") (pin "1") (pinfunction "B_1") (pintype "passive"))
      (node (ref "R29") (pin "2") (pinfunction "2_2") (pintype "passive"))
      (node (ref "R30") (pin "2") (pinfunction "2_2") (pintype "passive"))
    )
    (net (code "64") (name "Net-(Q7-E)") (class "Default")
      (node (ref "Q7") (pin "2") (pinfunction "E_2") (pintype "passive"))
      (node (ref "R31") (pin "2") (pinfunction "2_2") (pintype "passive"))
      (node (ref "R32") (pin "2") (pinfunction "2_2") (pintype "passive"))
      (node (ref "R33") (pin "2") (pinfunction "2_2") (pintype "passive"))
    )
    (net (code "65") (name "Net-(Q8-B)") (class "Default")
      (node (ref "Q8") (pin "1") (pinfunction "B_1") (pintype "passive"))
      (node (ref "R24") (pin "2") (pinfunction "2_2") (pintype "passive"))
      (node (ref "R25") (pin "2") (pinfunction "2_2") (pintype "passive"))
    )
    (net (code "66") (name "Net-(Q8-E)") (class "Default")
      (node (ref "Q8") (pin "2") (pinfunction "E_2") (pintype "passive"))
      (node (ref "R26") (pin "2") (pinfunction "2_2") (pintype "passive"))
      (node (ref "R27") (pin "2") (pinfunction "2_2") (pintype "passive"))
      (node (ref "R28") (pin "2") (pinfunction "2_2") (pintype "passive"))
    )
    (net (code "67") (name "Net-(R18-Pad2)") (class "Default")
      (node (ref "R18") (pin "2") (pinfunction "2_2") (pintype "passive"))
      (node (ref "R22") (pin "2") (pinfunction "2_2") (pintype "passive"))
    )
    (net (code "68") (name "Net-(T2-B)") (class "Default")
      (node (ref "C2") (pin "2") (pinfunction "2_2") (pintype "passive"))
      (node (ref "R18") (pin "1") (pinfunction "1_1") (pintype "passive"))
      (node (ref "R19") (pin "2") (pinfunction "2_2") (pintype "passive"))
      (node (ref "T2") (pin "1") (pinfunction "B_1") (pintype "passive"))
    )
    (net (code "69") (name "Net-(U$1-A0)") (class "Default")
      (node (ref "U$1") (pin "P20") (pinfunction "A0_P20") (pintype "bidirectional"))
      (node (ref "U1") (pin "P5") (pinfunction "IO_L20P_7_P5") (pintype "bidirectional"))
    )
    (net (code "70") (name "Net-(U$1-A1)") (class "Default")
      (node (ref "U$1") (pin "P19") (pinfunction "A1_P19") (pintype "bidirectional"))
      (node (ref "U1") (pin "P4") (pinfunction "IOVREF_7_P4") (pintype "bidirectional"))
    )
    (net (code "71") (name "Net-(U$1-A2)") (class "Default")
      (node (ref "U$1") (pin "P18") (pinfunction "A2_P18") (pintype "bidirectional"))
      (node (ref "U1") (pin "P2") (pinfunction "IO_L01N_7VRP_7_P2") (pintype "bidirectional"))
    )
    (net (code "72") (name "Net-(U$1-A3)") (class "Default")
      (node (ref "U$1") (pin "P17") (pinfunction "A3_P17") (pintype "bidirectional"))
      (node (ref "U1") (pin "P1") (pinfunction "IO_L01P_7VRN_7_P1") (pintype "bidirectional"))
    )
    (net (code "73") (name "Net-(U$1-A4)") (class "Default")
      (node (ref "U$1") (pin "P16") (pinfunction "A4_P16") (pintype "bidirectional"))
      (node (ref "U1") (pin "P36") (pinfunction "IO_L01N_6VRP_6_P36") (pintype "bidirectional"))
    )
    (net (code "74") (name "Net-(U$1-A5)") (class "Default")
      (node (ref "U$1") (pin "P15") (pinfunction "A5_P15") (pintype "bidirectional"))
      (node (ref "U1") (pin "P35") (pinfunction "IO_L01P_6VRN_6_P35") (pintype "bidirectional"))
    )
    (net (code "75") (name "Net-(U$1-A6)") (class "Default")
      (node (ref "U$1") (pin "P14") (pinfunction "A6_P14") (pintype "bidirectional"))
      (node (ref "U1") (pin "P33") (pinfunction "IO_L20N_6_P33") (pintype "bidirectional"))
    )
    (net (code "76") (name "Net-(U$1-A7)") (class "Default")
      (node (ref "U$1") (pin "P13") (pinfunction "A7_P13") (pintype "bidirectional"))
      (node (ref "U1") (pin "P32") (pinfunction "IO_L20P_6_P32") (pintype "bidirectional"))
    )
    (net (code "77") (name "Net-(U$1-A8)") (class "Default")
      (node (ref "U$1") (pin "P3") (pinfunction "A8_P3") (pintype "bidirectional"))
      (node (ref "U1") (pin "P21") (pinfunction "IO_L40N_6_P21") (pintype "bidirectional"))
    )
    (net (code "78") (name "Net-(U$1-A9)") (class "Default")
      (node (ref "U$1") (pin "P2") (pinfunction "A9_P2") (pintype "bidirectional"))
      (node (ref "U1") (pin "P20") (pinfunction "IO_L40P_6VREF_6_P20") (pintype "bidirectional"))
    )
    (net (code "79") (name "Net-(U$1-A10)") (class "Default")
      (node (ref "U$1") (pin "P31") (pinfunction "A10_P31") (pintype "bidirectional"))
      (node (ref "U1") (pin "P15") (pinfunction "IO_L24N_7_P15") (pintype "bidirectional"))
    )
    (net (code "80") (name "Net-(U$1-A11)") (class "Default")
      (node (ref "U$1") (pin "P1") (pinfunction "A11_P1") (pintype "bidirectional"))
      (node (ref "U1") (pin "P18") (pinfunction "IO_L40N_7VREF_7_P18") (pintype "bidirectional"))
    )
    (net (code "81") (name "Net-(U$1-A12)") (class "Default")
      (node (ref "U$1") (pin "P12") (pinfunction "A12_P12") (pintype "bidirectional"))
      (node (ref "U1") (pin "P31") (pinfunction "IO_L21N_6_P31") (pintype "bidirectional"))
    )
    (net (code "82") (name "Net-(U$1-A13)") (class "Default")
      (node (ref "U$1") (pin "P4") (pinfunction "A13_P4") (pintype "bidirectional"))
      (node (ref "U1") (pin "P23") (pinfunction "IO_L24P_6_P23") (pintype "bidirectional"))
    )
    (net (code "83") (name "Net-(U$1-A14)") (class "Default")
      (node (ref "U$1") (pin "P11") (pinfunction "A14_P11") (pintype "bidirectional"))
      (node (ref "U1") (pin "P30") (pinfunction "IO_L21P_6_P30") (pintype "bidirectional"))
    )
    (net (code "84") (name "Net-(U$1-A15)") (class "Default")
      (node (ref "U$1") (pin "P7") (pinfunction "A15_P7") (pintype "bidirectional"))
      (node (ref "U1") (pin "P26") (pinfunction "IO_L23N_6_P26") (pintype "bidirectional"))
    )
    (net (code "85") (name "Net-(U$1-A16)") (class "Default")
      (node (ref "U$1") (pin "P10") (pinfunction "A16_P10") (pintype "bidirectional"))
      (node (ref "U1") (pin "P28") (pinfunction "IO_L22N_6_P28") (pintype "bidirectional"))
    )
    (net (code "86") (name "Net-(U$1-A17)") (class "Default")
      (node (ref "U$1") (pin "P6") (pinfunction "A17_P6") (pintype "bidirectional"))
      (node (ref "U1") (pin "P25") (pinfunction "IO_L23P_6_P25") (pintype "bidirectional"))
    )
    (net (code "87") (name "Net-(U$1-A18)") (class "Default")
      (node (ref "U$1") (pin "P9") (pinfunction "A18_P9") (pintype "bidirectional"))
      (node (ref "U1") (pin "P27") (pinfunction "IO_L22P_6_P27") (pintype "bidirectional"))
    )
    (net (code "88") (name "Net-(U$1-DQ0)") (class "Default")
      (node (ref "U$1") (pin "P21") (pinfunction "DQ0_P21") (pintype "bidirectional"))
      (node (ref "U1") (pin "P6") (pinfunction "IO_L20N_7_P6") (pintype "bidirectional"))
    )
    (net (code "89") (name "Net-(U$1-DQ1)") (class "Default")
      (node (ref "U$1") (pin "P22") (pinfunction "DQ1_P22") (pintype "bidirectional"))
      (node (ref "U1") (pin "P7") (pinfunction "IO_L21P_7_P7") (pintype "bidirectional"))
    )
    (net (code "90") (name "Net-(U$1-DQ2)") (class "Default")
      (node (ref "U$1") (pin "P23") (pinfunction "DQ2_P23") (pintype "bidirectional"))
      (node (ref "U1") (pin "P8") (pinfunction "IO_L21N_7_P8") (pintype "bidirectional"))
    )
    (net (code "91") (name "Net-(U$1-DQ3)") (class "Default")
      (node (ref "U$1") (pin "P25") (pinfunction "DQ3_P25") (pintype "bidirectional"))
      (node (ref "U1") (pin "P10") (pinfunction "IO_L22P_7_P10") (pintype "bidirectional"))
    )
    (net (code "92") (name "Net-(U$1-DQ4)") (class "Default")
      (node (ref "U$1") (pin "P26") (pinfunction "DQ4_P26") (pintype "bidirectional"))
      (node (ref "U1") (pin "P11") (pinfunction "IO_L22N_7_P11") (pintype "bidirectional"))
    )
    (net (code "93") (name "Net-(U$1-DQ5)") (class "Default")
      (node (ref "U$1") (pin "P27") (pinfunction "DQ5_P27") (pintype "bidirectional"))
      (node (ref "U1") (pin "P12") (pinfunction "IO_L23P_7_P12") (pintype "bidirectional"))
    )
    (net (code "94") (name "Net-(U$1-DQ6)") (class "Default")
      (node (ref "U$1") (pin "P28") (pinfunction "DQ6_P28") (pintype "bidirectional"))
      (node (ref "U1") (pin "P13") (pinfunction "IO_L23N_7_P13") (pintype "bidirectional"))
    )
    (net (code "95") (name "Net-(U$1-DQ7)") (class "Default")
      (node (ref "U$1") (pin "P29") (pinfunction "DQ7_P29") (pintype "bidirectional"))
      (node (ref "U1") (pin "P14") (pinfunction "IO_L24P_7_P14") (pintype "bidirectional"))
    )
    (net (code "96") (name "Net-(U$1-OE)") (class "Default")
      (node (ref "U$1") (pin "P32") (pinfunction "OE_P32") (pintype "bidirectional"))
      (node (ref "U1") (pin "P17") (pinfunction "IO_L40P_7_P17") (pintype "bidirectional"))
    )
    (net (code "97") (name "Net-(U$1-WE)") (class "Default")
      (node (ref "U$1") (pin "P5") (pinfunction "WE_P5") (pintype "bidirectional"))
      (node (ref "U1") (pin "P24") (pinfunction "IO_L24N_6VREF_6_P24") (pintype "bidirectional"))
    )
    (net (code "98") (name "Net-(U1I-IO_L32P_5GCLK2)") (class "Default")
      (node (ref "U$2") (pin "OUT") (pinfunction "OUT_OUT") (pintype "output"))
      (node (ref "U1") (pin "P52") (pinfunction "IO_L32P_5GCLK2_P52") (pintype "bidirectional"))
    )
    (net (code "99") (name "Net-(U1N-TCK)") (class "Default")
      (node (ref "R2") (pin "1") (pinfunction "1_1") (pintype "passive"))
      (node (ref "U1") (pin "P110") (pinfunction "TCK_P110") (pintype "bidirectional"))
    )
    (net (code "100") (name "Net-(U1N-TDI)") (class "Default")
      (node (ref "R1") (pin "1") (pinfunction "1_1") (pintype "passive"))
      (node (ref "U1") (pin "P144") (pinfunction "TDI_P144") (pintype "bidirectional"))
    )
    (net (code "101") (name "Net-(U1N-TMS)") (class "Default")
      (node (ref "R3") (pin "1") (pinfunction "1_1") (pintype "passive"))
      (node (ref "U1") (pin "P111") (pinfunction "TMS_P111") (pintype "bidirectional"))
    )
    (net (code "102") (name "Net-(X4A-F)") (class "Default")
      (node (ref "R40") (pin "2") (pinfunction "2_2") (pintype "passive"))
      (node (ref "X4") (pin "1") (pinfunction "F_1") (pintype "passive"))
    )
    (net (code "103") (name "Net-(X4B-F)") (class "Default")
      (node (ref "R41") (pin "2") (pinfunction "2_2") (pintype "passive"))
      (node (ref "X4") (pin "2") (pinfunction "F_2") (pintype "passive"))
    )
    (net (code "104") (name "Net-(X4C-F)") (class "Default")
      (node (ref "R42") (pin "2") (pinfunction "2_2") (pintype "passive"))
      (node (ref "X4") (pin "3") (pinfunction "F_3") (pintype "passive"))
    )
    (net (code "105") (name "Net-(X4D-F)") (class "Default")
      (node (ref "R43") (pin "2") (pinfunction "2_2") (pintype "passive"))
      (node (ref "X4") (pin "4") (pinfunction "F_4") (pintype "passive"))
    )
    (net (code "106") (name "Net-(X4F-F)") (class "Default")
      (node (ref "R44") (pin "2") (pinfunction "2_2") (pintype "passive"))
      (node (ref "X4") (pin "6") (pinfunction "F_6") (pintype "passive"))
    )
    (net (code "107") (name "Net-(X4G-F)") (class "Default")
      (node (ref "R45") (pin "2") (pinfunction "2_2") (pintype "passive"))
      (node (ref "X4") (pin "7") (pinfunction "F_7") (pintype "passive"))
    )
    (net (code "108") (name "Net-(X5A-F)") (class "Default")
      (node (ref "R46") (pin "1") (pinfunction "1_1") (pintype "passive"))
      (node (ref "X5") (pin "1") (pinfunction "F_1") (pintype "passive"))
    )
    (net (code "109") (name "Net-(X5B-F)") (class "Default")
      (node (ref "R39") (pin "1") (pinfunction "1_1") (pintype "passive"))
      (node (ref "X5") (pin "2") (pinfunction "F_2") (pintype "passive"))
    )
    (net (code "110") (name "Net-(X5C-F)") (class "Default")
      (node (ref "R38") (pin "1") (pinfunction "1_1") (pintype "passive"))
      (node (ref "X5") (pin "3") (pinfunction "F_3") (pintype "passive"))
    )
    (net (code "111") (name "Net-(X5D-F)") (class "Default")
      (node (ref "R37") (pin "1") (pinfunction "1_1") (pintype "passive"))
      (node (ref "X5") (pin "4") (pinfunction "F_4") (pintype "passive"))
    )
    (net (code "112") (name "Net-(X5F-F)") (class "Default")
      (node (ref "R36") (pin "1") (pinfunction "1_1") (pintype "passive"))
      (node (ref "X5") (pin "6") (pinfunction "F_6") (pintype "passive"))
    )
    (net (code "113") (name "Net-(X5G-F)") (class "Default")
      (node (ref "R35") (pin "1") (pinfunction "1_1") (pintype "passive"))
      (node (ref "X5") (pin "7") (pinfunction "F_7") (pintype "passive"))
    )
    (net (code "114") (name "unconnected-(IC1-NC.1-Pad2)") (class "Default")
      (node (ref "IC1") (pin "2") (pinfunction "NC.1_2") (pintype "bidirectional"))
    )
    (net (code "115") (name "unconnected-(IC1-NC.2-Pad9)") (class "Default")
      (node (ref "IC1") (pin "9") (pinfunction "NC.2_9") (pintype "bidirectional"))
    )
    (net (code "116") (name "unconnected-(IC1-NC.3-Pad12)") (class "Default")
      (node (ref "IC1") (pin "12") (pinfunction "NC.3_12") (pintype "bidirectional"))
    )
    (net (code "117") (name "unconnected-(IC1-NC.4-Pad14)") (class "Default")
      (node (ref "IC1") (pin "14") (pinfunction "NC.4_14") (pintype "bidirectional"))
    )
    (net (code "118") (name "unconnected-(IC1-NC.5-Pad15)") (class "Default")
      (node (ref "IC1") (pin "15") (pinfunction "NC.5_15") (pintype "bidirectional"))
    )
    (net (code "119") (name "unconnected-(IC1-NC.6-Pad16)") (class "Default")
      (node (ref "IC1") (pin "16") (pinfunction "NC.6_16") (pintype "bidirectional"))
    )
    (net (code "120") (name "unconnected-(IC1-{slash}CEO-Pad13)") (class "Default")
      (node (ref "IC1") (pin "13") (pinfunction "/CEO_13") (pintype "bidirectional"))
    )
    (net (code "121") (name "unconnected-(REG1.2-VOUT2-Pad2)") (class "Default")
      (node (ref "REG1.2") (pin "2") (pinfunction "VOUT2_2") (pintype "bidirectional"))
    )
    (net (code "122") (name "unconnected-(REG2.5-VOUT2-Pad2)") (class "Default")
      (node (ref "REG2.5") (pin "2") (pinfunction "VOUT2_2") (pintype "bidirectional"))
    )
    (net (code "123") (name "unconnected-(U$2-TRI-PadENA)") (class "Default")
      (node (ref "U$2") (pin "ENA") (pinfunction "TRI_ENA") (pintype "input"))
    )
    (net (code "124") (name "unconnected-(U1A-IO_L01N_0VRP_0-PadP141)") (class "Default")
      (node (ref "U1") (pin "P141") (pinfunction "IO_L01N_0VRP_0_P141") (pintype "bidirectional"))
    )
    (net (code "125") (name "unconnected-(U1A-IO_L01P_0VRN_0-PadP140)") (class "Default")
      (node (ref "U1") (pin "P140") (pinfunction "IO_L01P_0VRN_0_P140") (pintype "bidirectional"))
    )
    (net (code "126") (name "unconnected-(U1A-IO_L27N_0-PadP137)") (class "Default")
      (node (ref "U1") (pin "P137") (pinfunction "IO_L27N_0_P137") (pintype "bidirectional"))
    )
    (net (code "127") (name "unconnected-(U1A-IO_L27P_0-PadP135)") (class "Default")
      (node (ref "U1") (pin "P135") (pinfunction "IO_L27P_0_P135") (pintype "bidirectional"))
    )
    (net (code "128") (name "unconnected-(U1A-IO_L30N_0-PadP132)") (class "Default")
      (node (ref "U1") (pin "P132") (pinfunction "IO_L30N_0_P132") (pintype "bidirectional"))
    )
    (net (code "129") (name "unconnected-(U1A-IO_L30P_0-PadP131)") (class "Default")
      (node (ref "U1") (pin "P131") (pinfunction "IO_L30P_0_P131") (pintype "bidirectional"))
    )
    (net (code "130") (name "unconnected-(U1A-IO_L31N_0-PadP130)") (class "Default")
      (node (ref "U1") (pin "P130") (pinfunction "IO_L31N_0_P130") (pintype "bidirectional"))
    )
    (net (code "131") (name "unconnected-(U1A-IO_L31P_0VREF_0-PadP129)") (class "Default")
      (node (ref "U1") (pin "P129") (pinfunction "IO_L31P_0VREF_0_P129") (pintype "bidirectional"))
    )
    (net (code "132") (name "unconnected-(U1A-IO_L32N_0GCLK7-PadP128)") (class "Default")
      (node (ref "U1") (pin "P128") (pinfunction "IO_L32N_0GCLK7_P128") (pintype "bidirectional"))
    )
    (net (code "133") (name "unconnected-(U1A-IO_L32P_0GCLK6-PadP127)") (class "Default")
      (node (ref "U1") (pin "P127") (pinfunction "IO_L32P_0GCLK6_P127") (pintype "bidirectional"))
    )
    (net (code "134") (name "unconnected-(U1C-IO-PadP116)") (class "Default")
      (node (ref "U1") (pin "P116") (pinfunction "IO_P116") (pintype "bidirectional"))
    )
    (net (code "135") (name "unconnected-(U1C-IO_L01N_1VRP_1-PadP113)") (class "Default")
      (node (ref "U1") (pin "P113") (pinfunction "IO_L01N_1VRP_1_P113") (pintype "bidirectional"))
    )
    (net (code "136") (name "unconnected-(U1C-IO_L01P_1VRN_1-PadP112)") (class "Default")
      (node (ref "U1") (pin "P112") (pinfunction "IO_L01P_1VRN_1_P112") (pintype "bidirectional"))
    )
    (net (code "137") (name "unconnected-(U1C-IO_L28N_1-PadP119)") (class "Default")
      (node (ref "U1") (pin "P119") (pinfunction "IO_L28N_1_P119") (pintype "bidirectional"))
    )
    (net (code "138") (name "unconnected-(U1C-IO_L28P_1-PadP118)") (class "Default")
      (node (ref "U1") (pin "P118") (pinfunction "IO_L28P_1_P118") (pintype "bidirectional"))
    )
    (net (code "139") (name "unconnected-(U1C-IO_L31N_1VREF_1-PadP123)") (class "Default")
      (node (ref "U1") (pin "P123") (pinfunction "IO_L31N_1VREF_1_P123") (pintype "bidirectional"))
    )
    (net (code "140") (name "unconnected-(U1C-IO_L31P_1-PadP122)") (class "Default")
      (node (ref "U1") (pin "P122") (pinfunction "IO_L31P_1_P122") (pintype "bidirectional"))
    )
    (net (code "141") (name "unconnected-(U1C-IO_L32N_1GCLK5-PadP125)") (class "Default")
      (node (ref "U1") (pin "P125") (pinfunction "IO_L32N_1GCLK5_P125") (pintype "bidirectional"))
    )
    (net (code "142") (name "unconnected-(U1C-IO_L32P_1GCLK4-PadP124)") (class "Default")
      (node (ref "U1") (pin "P124") (pinfunction "IO_L32P_1GCLK4_P124") (pintype "bidirectional"))
    )
    (net (code "143") (name "unconnected-(U1D-IO_L01N_2VRP_2-PadP108)") (class "Default")
      (node (ref "U1") (pin "P108") (pinfunction "IO_L01N_2VRP_2_P108") (pintype "bidirectional"))
    )
    (net (code "144") (name "unconnected-(U1D-IO_L01P_2VRN_2-PadP107)") (class "Default")
      (node (ref "U1") (pin "P107") (pinfunction "IO_L01P_2VRN_2_P107") (pintype "bidirectional"))
    )
    (net (code "145") (name "unconnected-(U1D-IO_L20N_2-PadP105)") (class "Default")
      (node (ref "U1") (pin "P105") (pinfunction "IO_L20N_2_P105") (pintype "bidirectional"))
    )
    (net (code "146") (name "unconnected-(U1D-IO_L20P_2-PadP104)") (class "Default")
      (node (ref "U1") (pin "P104") (pinfunction "IO_L20P_2_P104") (pintype "bidirectional"))
    )
    (net (code "147") (name "unconnected-(U1D-IO_L21N_2-PadP103)") (class "Default")
      (node (ref "U1") (pin "P103") (pinfunction "IO_L21N_2_P103") (pintype "bidirectional"))
    )
    (net (code "148") (name "unconnected-(U1D-IO_L21P_2-PadP102)") (class "Default")
      (node (ref "U1") (pin "P102") (pinfunction "IO_L21P_2_P102") (pintype "bidirectional"))
    )
    (net (code "149") (name "unconnected-(U1D-IO_L22N_2-PadP100)") (class "Default")
      (node (ref "U1") (pin "P100") (pinfunction "IO_L22N_2_P100") (pintype "bidirectional"))
    )
    (net (code "150") (name "unconnected-(U1D-IO_L22P_2-PadP99)") (class "Default")
      (node (ref "U1") (pin "P99") (pinfunction "IO_L22P_2_P99") (pintype "bidirectional"))
    )
    (net (code "151") (name "unconnected-(U1D-IO_L23N_2VREF_2-PadP98)") (class "Default")
      (node (ref "U1") (pin "P98") (pinfunction "IO_L23N_2VREF_2_P98") (pintype "bidirectional"))
    )
    (net (code "152") (name "unconnected-(U1D-IO_L23P_2-PadP97)") (class "Default")
      (node (ref "U1") (pin "P97") (pinfunction "IO_L23P_2_P97") (pintype "bidirectional"))
    )
    (net (code "153") (name "unconnected-(U1D-IO_L24N_2-PadP96)") (class "Default")
      (node (ref "U1") (pin "P96") (pinfunction "IO_L24N_2_P96") (pintype "bidirectional"))
    )
    (net (code "154") (name "unconnected-(U1D-IO_L24P_2-PadP95)") (class "Default")
      (node (ref "U1") (pin "P95") (pinfunction "IO_L24P_2_P95") (pintype "bidirectional"))
    )
    (net (code "155") (name "unconnected-(U1D-IO_L40N_2-PadP93)") (class "Default")
      (node (ref "U1") (pin "P93") (pinfunction "IO_L40N_2_P93") (pintype "bidirectional"))
    )
    (net (code "156") (name "unconnected-(U1D-IO_L40P_2VREF_2-PadP92)") (class "Default")
      (node (ref "U1") (pin "P92") (pinfunction "IO_L40P_2VREF_2_P92") (pintype "bidirectional"))
    )
    (net (code "157") (name "unconnected-(U1F-IO-PadP76)") (class "Default")
      (node (ref "U1") (pin "P76") (pinfunction "IO_P76") (pintype "bidirectional"))
    )
    (net (code "158") (name "unconnected-(U1F-IO_L01N_3VRP_3-PadP74)") (class "Default")
      (node (ref "U1") (pin "P74") (pinfunction "IO_L01N_3VRP_3_P74") (pintype "bidirectional"))
    )
    (net (code "159") (name "unconnected-(U1F-IO_L01P_3VRN_3-PadP73)") (class "Default")
      (node (ref "U1") (pin "P73") (pinfunction "IO_L01P_3VRN_3_P73") (pintype "bidirectional"))
    )
    (net (code "160") (name "unconnected-(U1F-IO_L20N_3-PadP78)") (class "Default")
      (node (ref "U1") (pin "P78") (pinfunction "IO_L20N_3_P78") (pintype "bidirectional"))
    )
    (net (code "161") (name "unconnected-(U1F-IO_L20P_3-PadP77)") (class "Default")
      (node (ref "U1") (pin "P77") (pinfunction "IO_L20P_3_P77") (pintype "bidirectional"))
    )
    (net (code "162") (name "unconnected-(U1F-IO_L21N_3-PadP80)") (class "Default")
      (node (ref "U1") (pin "P80") (pinfunction "IO_L21N_3_P80") (pintype "bidirectional"))
    )
    (net (code "163") (name "unconnected-(U1F-IO_L21P_3-PadP79)") (class "Default")
      (node (ref "U1") (pin "P79") (pinfunction "IO_L21P_3_P79") (pintype "bidirectional"))
    )
    (net (code "164") (name "unconnected-(U1F-IO_L22N_3-PadP83)") (class "Default")
      (node (ref "U1") (pin "P83") (pinfunction "IO_L22N_3_P83") (pintype "bidirectional"))
    )
    (net (code "165") (name "unconnected-(U1F-IO_L22P_3-PadP82)") (class "Default")
      (node (ref "U1") (pin "P82") (pinfunction "IO_L22P_3_P82") (pintype "bidirectional"))
    )
    (net (code "166") (name "unconnected-(U1F-IO_L23N_3-PadP85)") (class "Default")
      (node (ref "U1") (pin "P85") (pinfunction "IO_L23N_3_P85") (pintype "bidirectional"))
    )
    (net (code "167") (name "unconnected-(U1F-IO_L23P_3VREF_3-PadP84)") (class "Default")
      (node (ref "U1") (pin "P84") (pinfunction "IO_L23P_3VREF_3_P84") (pintype "bidirectional"))
    )
    (net (code "168") (name "unconnected-(U1F-IO_L24N_3-PadP87)") (class "Default")
      (node (ref "U1") (pin "P87") (pinfunction "IO_L24N_3_P87") (pintype "bidirectional"))
    )
    (net (code "169") (name "unconnected-(U1F-IO_L24P_3-PadP86)") (class "Default")
      (node (ref "U1") (pin "P86") (pinfunction "IO_L24P_3_P86") (pintype "bidirectional"))
    )
    (net (code "170") (name "unconnected-(U1F-IO_L40N_3VREF_3-PadP90)") (class "Default")
      (node (ref "U1") (pin "P90") (pinfunction "IO_L40N_3VREF_3_P90") (pintype "bidirectional"))
    )
    (net (code "171") (name "unconnected-(U1F-IO_L40P_3-PadP89)") (class "Default")
      (node (ref "U1") (pin "P89") (pinfunction "IO_L40P_3_P89") (pintype "bidirectional"))
    )
    (net (code "172") (name "unconnected-(U1G-IOVREF_4-PadP70)") (class "Default")
      (node (ref "U1") (pin "P70") (pinfunction "IOVREF_4_P70") (pintype "bidirectional"))
    )
    (net (code "173") (name "unconnected-(U1G-IO_L01N_4VRP_4-PadP69)") (class "Default")
      (node (ref "U1") (pin "P69") (pinfunction "IO_L01N_4VRP_4_P69") (pintype "bidirectional"))
    )
    (net (code "174") (name "unconnected-(U1G-IO_L01P_4VRN_4-PadP68)") (class "Default")
      (node (ref "U1") (pin "P68") (pinfunction "IO_L01P_4VRN_4_P68") (pintype "bidirectional"))
    )
    (net (code "175") (name "unconnected-(U1G-IO_L27P_4D1-PadP63)") (class "Default")
      (node (ref "U1") (pin "P63") (pinfunction "IO_L27P_4D1_P63") (pintype "bidirectional"))
    )
    (net (code "176") (name "unconnected-(U1G-IO_L30N_4D2-PadP60)") (class "Default")
      (node (ref "U1") (pin "P60") (pinfunction "IO_L30N_4D2_P60") (pintype "bidirectional"))
    )
    (net (code "177") (name "unconnected-(U1G-IO_L30P_4D3-PadP59)") (class "Default")
      (node (ref "U1") (pin "P59") (pinfunction "IO_L30P_4D3_P59") (pintype "bidirectional"))
    )
    (net (code "178") (name "unconnected-(U1G-IO_L31P_4DOUTBUSY-PadP57)") (class "Default")
      (node (ref "U1") (pin "P57") (pinfunction "IO_L31P_4DOUTBUSY_P57") (pintype "bidirectional"))
    )
    (net (code "179") (name "unconnected-(U1G-IO_L32N_4GCLK1-PadP56)") (class "Default")
      (node (ref "U1") (pin "P56") (pinfunction "IO_L32N_4GCLK1_P56") (pintype "bidirectional"))
    )
    (net (code "180") (name "unconnected-(U1G-IO_L32P_4GCLK0-PadP55)") (class "Default")
      (node (ref "U1") (pin "P55") (pinfunction "IO_L32P_4GCLK0_P55") (pintype "bidirectional"))
    )
    (net (code "181") (name "unconnected-(U1I-IO_L28N_5D6-PadP47)") (class "Default")
      (node (ref "U1") (pin "P47") (pinfunction "IO_L28N_5D6_P47") (pintype "bidirectional"))
    )
    (net (code "182") (name "unconnected-(U1I-IO_L31N_5D4-PadP51)") (class "Default")
      (node (ref "U1") (pin "P51") (pinfunction "IO_L31N_5D4_P51") (pintype "bidirectional"))
    )
    (net (code "183") (name "unconnected-(U1I-IO_L31P_5D5-PadP50)") (class "Default")
      (node (ref "U1") (pin "P50") (pinfunction "IO_L31P_5D5_P50") (pintype "bidirectional"))
    )
    (net (code "184") (name "unconnected-(U1I-IO_L32N_5GCLK3-PadP53)") (class "Default")
      (node (ref "U1") (pin "P53") (pinfunction "IO_L32N_5GCLK3_P53") (pintype "bidirectional"))
    )
    (net (code "185") (name "unconnected-(U1N-HSWAP_EN-PadP142)") (class "Default")
      (node (ref "U1") (pin "P142") (pinfunction "HSWAP_EN_P142") (pintype "bidirectional"))
    )
    (net (code "186") (name "unconnected-(X1-3-Pad2)") (class "Default")
      (node (ref "X1") (pin "2") (pinfunction "3_2") (pintype "passive"))
    )
    (net (code "187") (name "unconnected-(X2-Pad10)") (class "Default")
      (node (ref "X2") (pin "10") (pinfunction "10_10") (pintype "passive"))
    )
    (net (code "188") (name "unconnected-(X2-Pad12)") (class "Default")
      (node (ref "X2") (pin "12") (pinfunction "12_12") (pintype "passive"))
    )
    (net (code "189") (name "unconnected-(X3-Pad2)") (class "Default")
      (node (ref "X3") (pin "2") (pinfunction "2_2") (pintype "passive"))
    )
    (net (code "190") (name "unconnected-(X3-Pad8)") (class "Default")
      (node (ref "X3") (pin "8") (pinfunction "8_8") (pintype "passive"))
    )
    (net (code "191") (name "unconnected-(X4-PadG2)") (class "Default")
      (node (ref "X4") (pin "G2") (pinfunction "G2_G2") (pintype "passive"))
    )
    (net (code "192") (name "unconnected-(X5-PadG2)") (class "Default")
      (node (ref "X5") (pin "G2") (pinfunction "G2_G2") (pintype "passive"))
    )
  )
)
